# Sensor_Temperatura.net
KiCad netlist of a schematic drawn in EAGLE
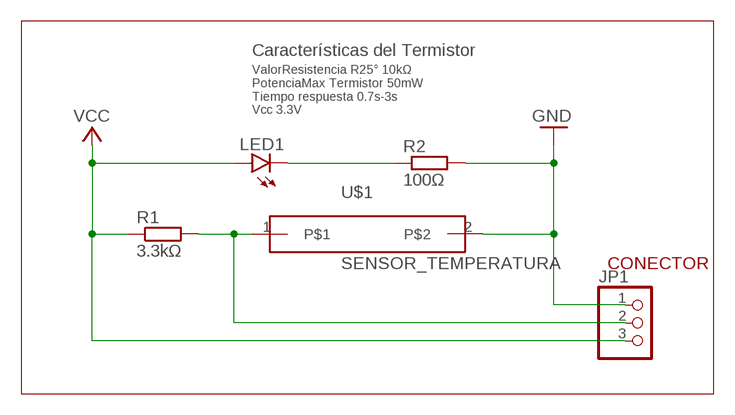
[diagram p0: schematic, sheet 1]

(export (version "E")
  (design (tool "Eeschema 10.0.6"))
  (components
    (comp (ref "JP1")
      (value "PINHD-1X3")
      (footprint "eagle-import:1X03")
      (fields (field (name "PARTNO") "PPPC031LFBN-RC"))
      (libsource (lib "eagle-import") (part "PINHD-1X3"))
    )
    (comp (ref "LED1")
      (value "LEDCHIP-LED0805")
      (footprint "eagle-import:CHIP-LED0805")
      (fields (field (name "PARTNO") "EAST2012GA0"))
      (libsource (lib "eagle-import") (part "LEDCHIP-LED0805"))
    )
    (comp (ref "R1")
      (value "3.3kΩ")
      (footprint "eagle-import:R0805")
      (fields (field (name "PARTNO") "RC0402FR-073K3L"))
      (libsource (lib "eagle-import") (part "R-EU_R0805"))
    )
    (comp (ref "R2")
      (value "100Ω")
      (footprint "eagle-import:R0805")
      (fields (field (name "PARTNO") "RC0805FR-07100RL"))
      (libsource (lib "eagle-import") (part "R-EU_R0805"))
    )
    (comp (ref "U$1")
      (value "SENSOR_TEMPERATURA")
      (footprint "eagle-import:1X02")
      (fields (field (name "PARTNO") "NTCLE305E4103SB"))
      (libsource (lib "eagle-import") (part "SENSOR_TEMPERATURA"))
    )
  )
  (nets
    (net (code "1") (name "GND") (class "Default")
      (node (ref "JP1") (pin "1") (pinfunction "1_1") (pintype "passive"))
      (node (ref "R2") (pin "2") (pinfunction "2_2") (pintype "passive"))
      (node (ref "U$1") (pin "2") (pinfunction "P$2_2") (pintype "passive"))
    )
    (net (code "2") (name "Net-(LED1-PadC)") (class "Default")
      (node (ref "LED1") (pin "C") (pinfunction "C_C") (pintype "passive"))
      (node (ref "R2") (pin "1") (pinfunction "1_1") (pintype "passive"))
    )
    (net (code "3") (name "Net-(U$1-P$1)") (class "Default")
      (node (ref "JP1") (pin "2") (pinfunction "2_2") (pintype "passive"))
      (node (ref "R1") (pin "2") (pinfunction "2_2") (pintype "passive"))
      (node (ref "U$1") (pin "1") (pinfunction "P$1_1") (pintype "passive"))
    )
    (net (code "4") (name "VCC") (class "Default")
      (node (ref "JP1") (pin "3") (pinfunction "3_3") (pintype "passive"))
      (node (ref "LED1") (pin "A") (pinfunction "A_A") (pintype "passive"))
      (node (ref "R1") (pin "1") (pinfunction "1_1") (pintype "passive"))
    )
  )
)
